# Balloon2.net
KiCad netlist of a schematic drawn in EAGLE
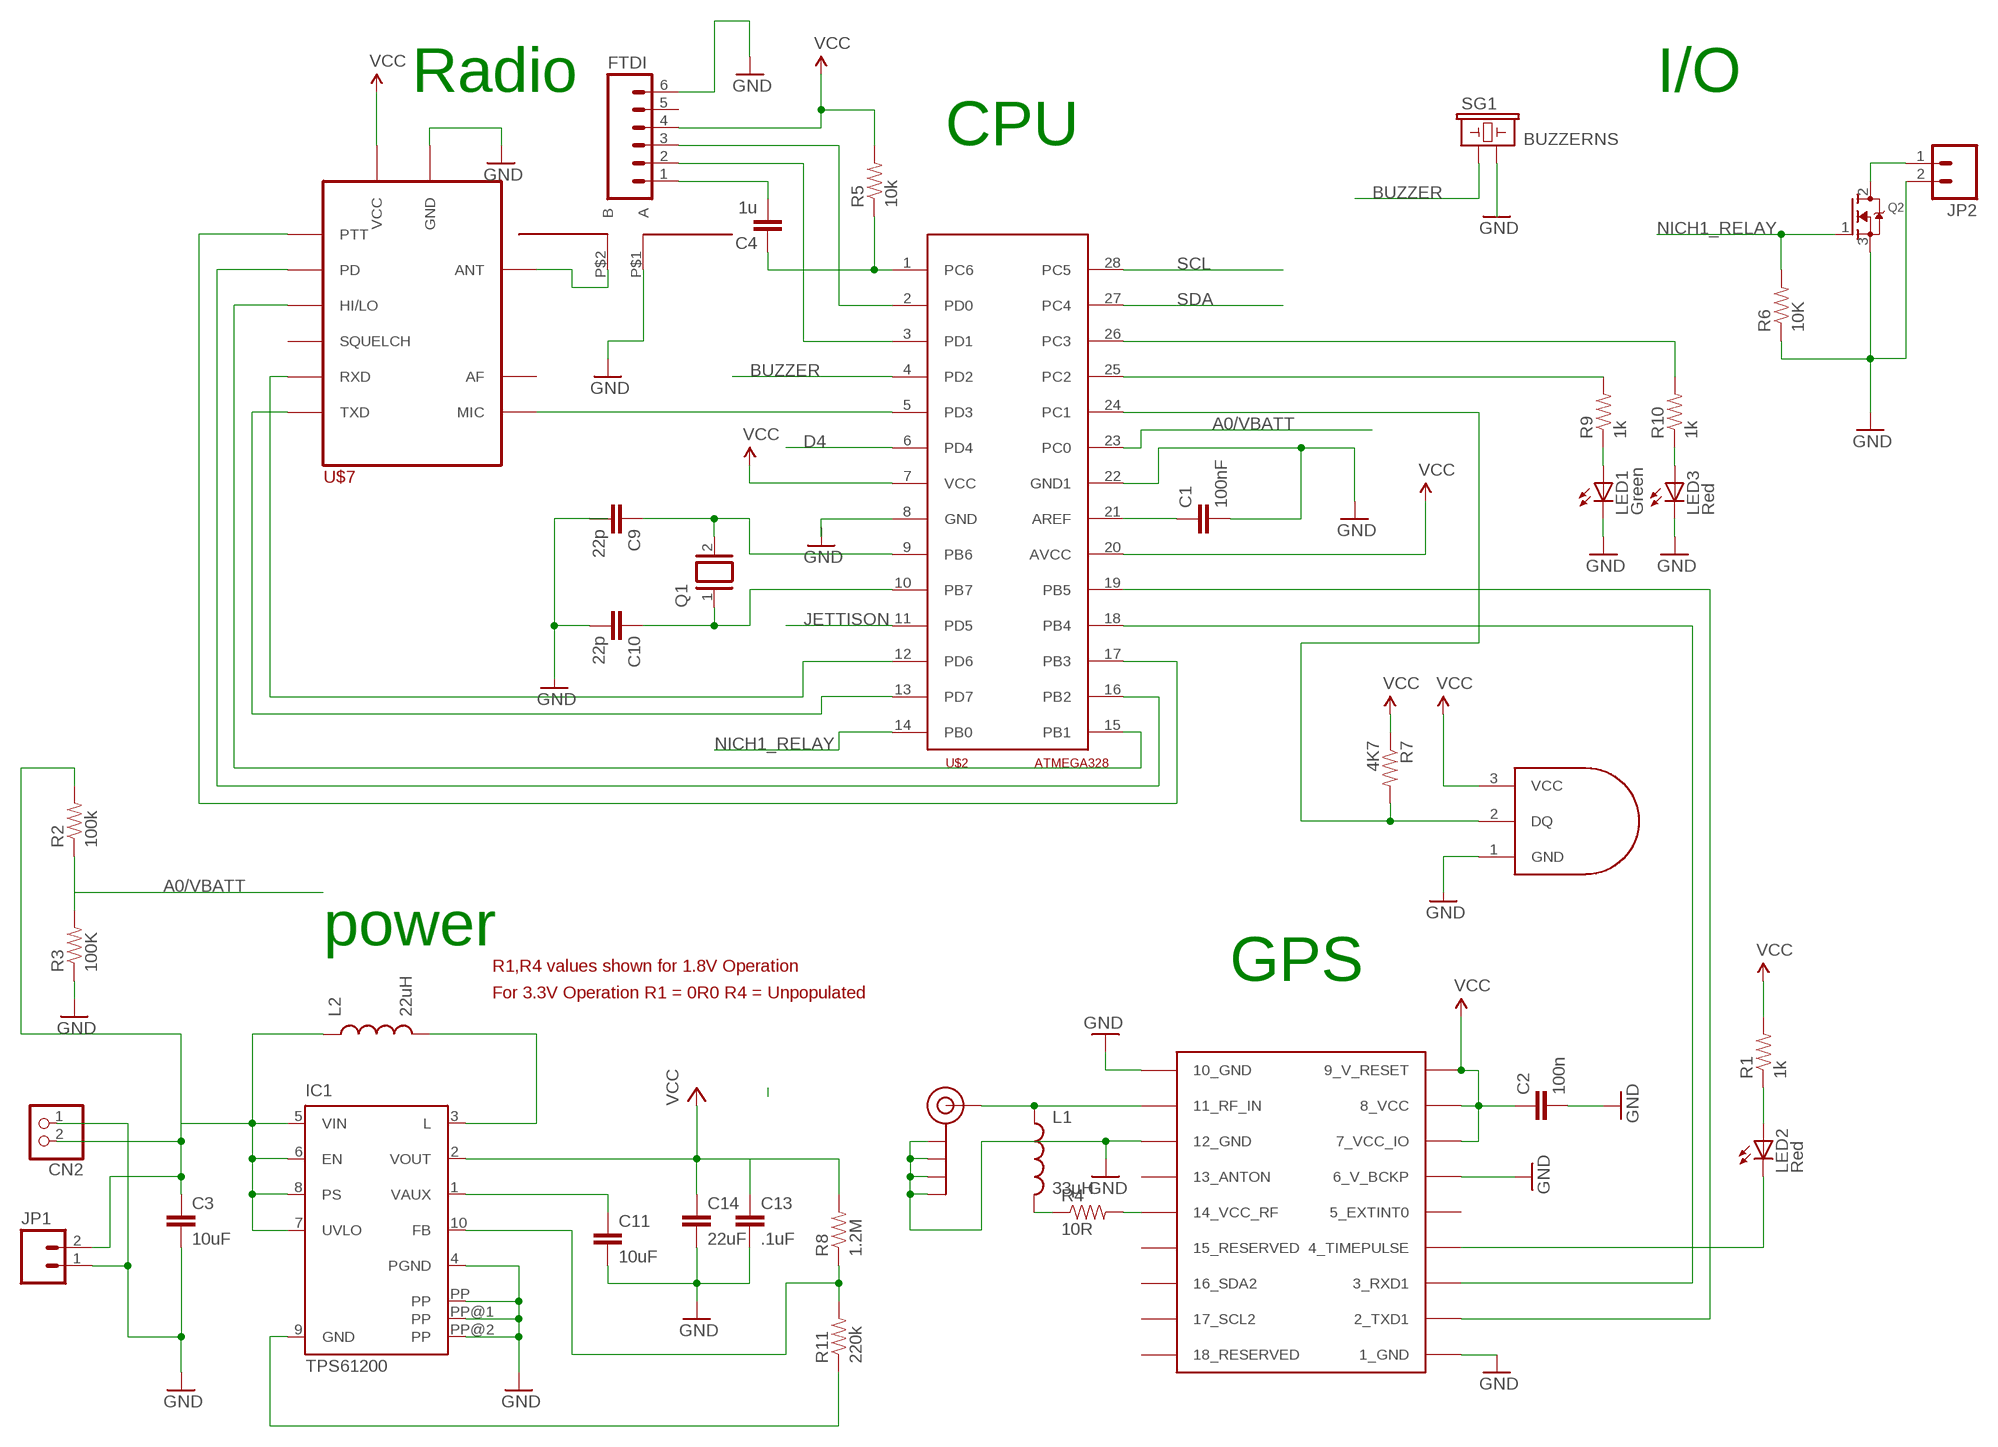
[diagram p0: schematic, sheet 1]

(export (version "E")
  (design (tool "Eeschema 10.0.6"))
  (components
    (comp (ref "C1")
      (value "100nF")
      (footprint "eagle-import:0805")
      (libsource (lib "eagle-import") (part "CAP0805"))
    )
    (comp (ref "C2")
      (value "100n")
      (footprint "eagle-import:0805")
      (libsource (lib "eagle-import") (part "CAP0805"))
    )
    (comp (ref "C3")
      (value "10uF")
      (footprint "eagle-import:0805")
      (libsource (lib "eagle-import") (part "CAP0805"))
    )
    (comp (ref "C4")
      (value "1u")
      (footprint "eagle-import:0805")
      (libsource (lib "eagle-import") (part "CAP0805"))
    )
    (comp (ref "C9")
      (value "22p")
      (footprint "eagle-import:0805")
      (libsource (lib "eagle-import") (part "CAP0805"))
    )
    (comp (ref "C10")
      (value "22p")
      (footprint "eagle-import:0805")
      (libsource (lib "eagle-import") (part "CAP0805"))
    )
    (comp (ref "C11")
      (value "10uF")
      (footprint "eagle-import:0805")
      (libsource (lib "eagle-import") (part "CAP0805"))
    )
    (comp (ref "C13")
      (value ".1uF")
      (footprint "eagle-import:0805")
      (libsource (lib "eagle-import") (part "CAP0805"))
    )
    (comp (ref "C14")
      (value "22uF")
      (footprint "eagle-import:0805")
      (libsource (lib "eagle-import") (part "CAP0805"))
    )
    (comp (ref "CN2")
      (value "JST_2PIN-SMT-RA")
      (footprint "eagle-import:JST-PH-2-SMT-RA")
      (libsource (lib "eagle-import") (part "JST_2PIN-SMT-RA"))
    )
    (comp (ref "FTDI")
      (value "M06SIP")
      (footprint "eagle-import:1X06")
      (libsource (lib "eagle-import") (part "M06SIP"))
    )
    (comp (ref "IC1")
      (value "TPS61200")
      (footprint "eagle-import:S-PDSO-N10")
      (fields (field (name "MPN") "TPS61200DRCT"))
      (libsource (lib "eagle-import") (part "TPS61200"))
    )
    (comp (ref "J$2")
      (value "SMA_EDGE")
      (footprint "eagle-import:SMA-EDGE")
      (libsource (lib "eagle-import") (part "SMA_EDGE"))
    )
    (comp (ref "JP1")
      (value "M02PTH")
      (footprint "eagle-import:1X02")
      (libsource (lib "eagle-import") (part "M02PTH"))
    )
    (comp (ref "JP2")
      (value "M02PTH")
      (footprint "eagle-import:1X02")
      (libsource (lib "eagle-import") (part "M02PTH"))
    )
    (comp (ref "L1")
      (value "33µH")
      (footprint "eagle-import:0805")
      (libsource (lib "eagle-import") (part "INDUCTOR0805"))
    )
    (comp (ref "L2")
      (value "22uH")
      (footprint "eagle-import:INDUCTOR-SRP4020")
      (libsource (lib "eagle-import") (part "INDUCTOR"))
    )
    (comp (ref "LED1")
      (value "Green")
      (footprint "eagle-import:CHIP-LED0805")
      (libsource (lib "eagle-import") (part "LEDCHIP-LED0805"))
    )
    (comp (ref "LED2")
      (value "Red")
      (footprint "eagle-import:CHIP-LED0805")
      (libsource (lib "eagle-import") (part "LEDCHIP-LED0805"))
    )
    (comp (ref "LED3")
      (value "Red")
      (footprint "eagle-import:CHIP-LED0805")
      (libsource (lib "eagle-import") (part "LEDCHIP-LED0805"))
    )
    (comp (ref "Q1")
      (value "XTAL/S")
      (footprint "eagle-import:QS")
      (libsource (lib "eagle-import") (part "XTAL/S"))
    )
    (comp (ref "Q2")
      (value "MOSFET-NGDS_TO220V")
      (footprint "eagle-import:TO220V")
      (libsource (lib "eagle-import") (part "MOSFET-NGDS_TO220V"))
    )
    (comp (ref "R1")
      (value "1k")
      (footprint "eagle-import:0805")
      (libsource (lib "eagle-import") (part "RESISTOR0805-RES"))
    )
    (comp (ref "R2")
      (value "100k")
      (footprint "eagle-import:0805")
      (libsource (lib "eagle-import") (part "RESISTOR0805-RES"))
    )
    (comp (ref "R3")
      (value "100K")
      (footprint "eagle-import:0805")
      (libsource (lib "eagle-import") (part "RESISTOR0805-RES"))
    )
    (comp (ref "R4")
      (value "10R")
      (footprint "eagle-import:0805")
      (libsource (lib "eagle-import") (part "RESISTOR0805-RES"))
    )
    (comp (ref "R5")
      (value "10k")
      (footprint "eagle-import:0805")
      (libsource (lib "eagle-import") (part "RESISTOR0805-RES"))
    )
    (comp (ref "R6")
      (value "10K")
      (footprint "eagle-import:0805")
      (libsource (lib "eagle-import") (part "RESISTOR0805-RES"))
    )
    (comp (ref "R7")
      (value "4K7")
      (footprint "eagle-import:0805")
      (libsource (lib "eagle-import") (part "RESISTOR0805-RES"))
    )
    (comp (ref "R8")
      (value "1.2M")
      (footprint "eagle-import:0805")
      (libsource (lib "eagle-import") (part "RESISTOR0805-RES"))
    )
    (comp (ref "R9")
      (value "1k")
      (footprint "eagle-import:0805")
      (libsource (lib "eagle-import") (part "RESISTOR0805-RES"))
    )
    (comp (ref "R10")
      (value "1k")
      (footprint "eagle-import:0805")
      (libsource (lib "eagle-import") (part "RESISTOR0805-RES"))
    )
    (comp (ref "R11")
      (value "220k")
      (footprint "eagle-import:0805")
      (libsource (lib "eagle-import") (part "RESISTOR0805-RES"))
    )
    (comp (ref "SG1")
      (value "BUZZERNS")
      (footprint "eagle-import:BUZZER-12MM-NS")
      (libsource (lib "eagle-import") (part "BUZZERNS"))
    )
    (comp (ref "U$1")
      (value "UBLOX_MAX")
      (footprint "eagle-import:UBLOX_MAX")
      (libsource (lib "eagle-import") (part "UBLOX_MAX"))
    )
    (comp (ref "U$2")
      (value "ATMEGA328")
      (footprint "eagle-import:DIL28")
      (libsource (lib "eagle-import") (part "ATMEGA328"))
    )
    (comp (ref "U$3")
      (value "DS18B20")
      (footprint "eagle-import:TO-92")
      (libsource (lib "eagle-import") (part "DS18B20"))
    )
    (comp (ref "U$4")
      (value "SOLDER-DIPOLE")
      (footprint "eagle-import:SOLDERED-DIPOLE-5MM")
      (libsource (lib "eagle-import") (part "SOLDER-DIPOLE"))
    )
    (comp (ref "U$7")
      (value "DORJI")
      (footprint "eagle-import:DORJI")
      (libsource (lib "eagle-import") (part "DORJI"))
    )
  )
  (nets
    (net (code "1") (name "/A0{slash}VBATT") (class "Default")
      (node (ref "R2") (pin "1") (pinfunction "1_1") (pintype "passive"))
      (node (ref "R3") (pin "2") (pinfunction "2_2") (pintype "passive"))
      (node (ref "U$2") (pin "23") (pinfunction "PC0_23") (pintype "bidirectional"))
    )
    (net (code "2") (name "/BUZZER") (class "Default")
      (node (ref "SG1") (pin "+") (pinfunction "1_+") (pintype "passive"))
      (node (ref "U$2") (pin "4") (pinfunction "PD2_4") (pintype "bidirectional"))
    )
    (net (code "3") (name "/D4") (class "Default")
      (node (ref "U$2") (pin "6") (pinfunction "PD4_6") (pintype "bidirectional"))
    )
    (net (code "4") (name "/JETTISON") (class "Default")
      (node (ref "U$2") (pin "11") (pinfunction "PD5_11") (pintype "bidirectional"))
    )
    (net (code "5") (name "/NICH1_RELAY") (class "Default")
      (node (ref "Q2") (pin "1") (pinfunction "G_1") (pintype "bidirectional"))
      (node (ref "R6") (pin "2") (pinfunction "2_2") (pintype "passive"))
      (node (ref "U$2") (pin "14") (pinfunction "PB0_14") (pintype "bidirectional"))
    )
    (net (code "6") (name "/SCL") (class "Default")
      (node (ref "U$2") (pin "28") (pinfunction "PC5_28") (pintype "bidirectional"))
    )
    (net (code "7") (name "/SDA") (class "Default")
      (node (ref "U$2") (pin "27") (pinfunction "PC4_27") (pintype "bidirectional"))
    )
    (net (code "8") (name "GND") (class "Default")
      (node (ref "C1") (pin "2") (pinfunction "2_2") (pintype "passive"))
      (node (ref "C11") (pin "2") (pinfunction "2_2") (pintype "passive"))
      (node (ref "C13") (pin "2") (pinfunction "2_2") (pintype "passive"))
      (node (ref "C14") (pin "2") (pinfunction "2_2") (pintype "passive"))
      (node (ref "C2") (pin "2") (pinfunction "2_2") (pintype "passive"))
      (node (ref "C3") (pin "2") (pinfunction "2_2") (pintype "passive"))
      (node (ref "CN2") (pin "1") (pinfunction "2_1") (pintype "passive"))
      (node (ref "FTDI") (pin "6") (pinfunction "6_6") (pintype "passive"))
      (node (ref "IC1") (pin "4") (pinfunction "PGND_4") (pintype "power_in"))
      (node (ref "IC1") (pin "PP") (pinfunction "PP_PP") (pintype "power_in"))
      (node (ref "IC1") (pin "PP@1") (pinfunction "PP_PP@1") (pintype "power_in"))
      (node (ref "IC1") (pin "PP@2") (pinfunction "PP_PP@2") (pintype "power_in"))
      (node (ref "J$2") (pin "GND@0") (pinfunction "GND_GND@0") (pintype "bidirectional"))
      (node (ref "J$2") (pin "GND@1") (pinfunction "GND_GND@1") (pintype "bidirectional"))
      (node (ref "J$2") (pin "GND@2") (pinfunction "GND_GND@2") (pintype "bidirectional"))
      (node (ref "J$2") (pin "GND@3") (pinfunction "GND_GND@3") (pintype "bidirectional"))
      (node (ref "JP1") (pin "1") (pinfunction "1_1") (pintype "passive"))
      (node (ref "JP2") (pin "2") (pinfunction "2_2") (pintype "passive"))
      (node (ref "LED1") (pin "C") (pinfunction "C_C") (pintype "passive"))
      (node (ref "LED3") (pin "C") (pinfunction "C_C") (pintype "passive"))
      (node (ref "Q2") (pin "3") (pinfunction "S_3") (pintype "bidirectional"))
      (node (ref "R3") (pin "1") (pinfunction "1_1") (pintype "passive"))
      (node (ref "R6") (pin "1") (pinfunction "1_1") (pintype "passive"))
      (node (ref "U$1") (pin "10_GND") (pinfunction "10_GND_10_GND") (pintype "power_in"))
      (node (ref "U$1") (pin "12_GND") (pinfunction "12_GND_12_GND") (pintype "power_in"))
      (node (ref "U$1") (pin "1_GND") (pinfunction "1_GND_1_GND") (pintype "power_in"))
      (node (ref "U$1") (pin "6_V_BCKP") (pinfunction "6_V_BCKP_6_V_BCKP") (pintype "bidirectional"))
      (node (ref "U$2") (pin "22") (pinfunction "GND1_22") (pintype "bidirectional"))
      (node (ref "U$4") (pin "P$1") (pinfunction "A_P$1") (pintype "bidirectional"))
      (node (ref "U$7") (pin "P$10") (pinfunction "GND_P$10") (pintype "bidirectional"))
      (node (ref "U$7") (pin "P$9") (pinfunction "GND_P$9") (pintype "bidirectional"))
    )
    (net (code "9") (name "Net-(C4-Pad2)") (class "Default")
      (node (ref "C4") (pin "2") (pinfunction "2_2") (pintype "passive"))
      (node (ref "FTDI") (pin "1") (pinfunction "1_1") (pintype "passive"))
    )
    (net (code "10") (name "Net-(CN2-1)") (class "Default")
      (node (ref "C3") (pin "1") (pinfunction "1_1") (pintype "passive"))
      (node (ref "CN2") (pin "2") (pinfunction "1_2") (pintype "passive"))
      (node (ref "IC1") (pin "5") (pinfunction "VIN_5") (pintype "input"))
      (node (ref "IC1") (pin "6") (pinfunction "EN_6") (pintype "input"))
      (node (ref "IC1") (pin "7") (pinfunction "UVLO_7") (pintype "input"))
      (node (ref "IC1") (pin "8") (pinfunction "PS_8") (pintype "input"))
      (node (ref "JP1") (pin "2") (pinfunction "2_2") (pintype "passive"))
      (node (ref "L2") (pin "P$1") (pinfunction "1_P$1") (pintype "passive"))
      (node (ref "R2") (pin "2") (pinfunction "2_2") (pintype "passive"))
    )
    (net (code "11") (name "Net-(IC1-FB)") (class "Default")
      (node (ref "IC1") (pin "10") (pinfunction "FB_10") (pintype "input"))
      (node (ref "R11") (pin "2") (pinfunction "2_2") (pintype "passive"))
      (node (ref "R8") (pin "1") (pinfunction "1_1") (pintype "passive"))
    )
    (net (code "12") (name "Net-(IC1-GND)") (class "Default")
      (node (ref "IC1") (pin "9") (pinfunction "GND_9") (pintype "power_in"))
      (node (ref "R11") (pin "1") (pinfunction "1_1") (pintype "passive"))
    )
    (net (code "13") (name "Net-(IC1-L)") (class "Default")
      (node (ref "IC1") (pin "3") (pinfunction "L_3") (pintype "input"))
      (node (ref "L2") (pin "P$2") (pinfunction "2_P$2") (pintype "passive"))
    )
    (net (code "14") (name "Net-(IC1-VAUX)") (class "Default")
      (node (ref "C11") (pin "1") (pinfunction "1_1") (pintype "passive"))
      (node (ref "IC1") (pin "1") (pinfunction "VAUX_1") (pintype "bidirectional"))
    )
    (net (code "15") (name "Net-(J$2-SIGNAL)") (class "Default")
      (node (ref "J$2") (pin "SIG") (pinfunction "SIGNAL_SIG") (pintype "bidirectional"))
      (node (ref "L1") (pin "1") (pinfunction "1_1") (pintype "passive"))
      (node (ref "U$1") (pin "11_RF_IN") (pinfunction "11_RF_IN_11_RF_IN") (pintype "bidirectional"))
    )
    (net (code "16") (name "Net-(L1-Pad2)") (class "Default")
      (node (ref "L1") (pin "2") (pinfunction "2_2") (pintype "passive"))
      (node (ref "R4") (pin "1") (pinfunction "1_1") (pintype "passive"))
    )
    (net (code "17") (name "Net-(LED1-PadA)") (class "Default")
      (node (ref "LED1") (pin "A") (pinfunction "A_A") (pintype "passive"))
      (node (ref "R9") (pin "1") (pinfunction "1_1") (pintype "passive"))
    )
    (net (code "18") (name "Net-(LED2-PadA)") (class "Default")
      (node (ref "LED2") (pin "A") (pinfunction "A_A") (pintype "passive"))
      (node (ref "R1") (pin "1") (pinfunction "1_1") (pintype "passive"))
    )
    (net (code "19") (name "Net-(LED2-PadC)") (class "Default")
      (node (ref "LED2") (pin "C") (pinfunction "C_C") (pintype "passive"))
      (node (ref "U$1") (pin "4_TIMEPULSE") (pinfunction "4_TIMEPULSE_4_TIMEPULSE") (pintype "bidirectional"))
    )
    (net (code "20") (name "Net-(LED3-PadA)") (class "Default")
      (node (ref "LED3") (pin "A") (pinfunction "A_A") (pintype "passive"))
      (node (ref "R10") (pin "1") (pinfunction "1_1") (pintype "passive"))
    )
    (net (code "21") (name "Net-(Q2-D)") (class "Default")
      (node (ref "JP2") (pin "1") (pinfunction "1_1") (pintype "passive"))
      (node (ref "Q2") (pin "2") (pinfunction "D_2") (pintype "bidirectional"))
    )
    (net (code "22") (name "Net-(R4-Pad2)") (class "Default")
      (node (ref "R4") (pin "2") (pinfunction "2_2") (pintype "passive"))
      (node (ref "U$1") (pin "14_VCC_RF") (pinfunction "14_VCC_RF_14_VCC_RF") (pintype "bidirectional"))
    )
    (net (code "23") (name "Net-(U$2-AREF)") (class "Default")
      (node (ref "C1") (pin "1") (pinfunction "1_1") (pintype "passive"))
      (node (ref "U$2") (pin "21") (pinfunction "AREF_21") (pintype "bidirectional"))
    )
    (net (code "24") (name "Net-(U$2-PB1)") (class "Default")
      (node (ref "U$2") (pin "15") (pinfunction "PB1_15") (pintype "bidirectional"))
      (node (ref "U$7") (pin "P$7") (pinfunction "HI/LO_P$7") (pintype "bidirectional"))
    )
    (net (code "25") (name "Net-(U$2-PB2)") (class "Default")
      (node (ref "U$2") (pin "16") (pinfunction "PB2_16") (pintype "bidirectional"))
      (node (ref "U$7") (pin "P$6") (pinfunction "PD_P$6") (pintype "bidirectional"))
    )
    (net (code "26") (name "Net-(U$2-PB3)") (class "Default")
      (node (ref "U$2") (pin "17") (pinfunction "PB3_17") (pintype "bidirectional"))
      (node (ref "U$7") (pin "P$5") (pinfunction "PTT_P$5") (pintype "bidirectional"))
    )
    (net (code "27") (name "Net-(U$2-PB4)") (class "Default")
      (node (ref "U$1") (pin "3_RXD1") (pinfunction "3_RXD1_3_RXD1") (pintype "bidirectional"))
      (node (ref "U$2") (pin "18") (pinfunction "PB4_18") (pintype "bidirectional"))
    )
    (net (code "28") (name "Net-(U$2-PB5)") (class "Default")
      (node (ref "U$1") (pin "2_TXD1") (pinfunction "2_TXD1_2_TXD1") (pintype "bidirectional"))
      (node (ref "U$2") (pin "19") (pinfunction "PB5_19") (pintype "bidirectional"))
    )
    (net (code "29") (name "Net-(U$2-PB6)") (class "Default")
      (node (ref "C9") (pin "1") (pinfunction "1_1") (pintype "passive"))
      (node (ref "Q1") (pin "2") (pinfunction "2_2") (pintype "passive"))
      (node (ref "U$2") (pin "9") (pinfunction "PB6_9") (pintype "bidirectional"))
    )
    (net (code "30") (name "Net-(U$2-PB7)") (class "Default")
      (node (ref "C10") (pin "1") (pinfunction "1_1") (pintype "passive"))
      (node (ref "Q1") (pin "1") (pinfunction "1_1") (pintype "passive"))
      (node (ref "U$2") (pin "10") (pinfunction "PB7_10") (pintype "bidirectional"))
    )
    (net (code "31") (name "Net-(U$2-PC1)") (class "Default")
      (node (ref "R7") (pin "2") (pinfunction "2_2") (pintype "passive"))
      (node (ref "U$2") (pin "24") (pinfunction "PC1_24") (pintype "bidirectional"))
      (node (ref "U$3") (pin "2") (pinfunction "DQ_2") (pintype "bidirectional"))
    )
    (net (code "32") (name "Net-(U$2-PC2)") (class "Default")
      (node (ref "R9") (pin "2") (pinfunction "2_2") (pintype "passive"))
      (node (ref "U$2") (pin "25") (pinfunction "PC2_25") (pintype "bidirectional"))
    )
    (net (code "33") (name "Net-(U$2-PC3)") (class "Default")
      (node (ref "R10") (pin "2") (pinfunction "2_2") (pintype "passive"))
      (node (ref "U$2") (pin "26") (pinfunction "PC3_26") (pintype "bidirectional"))
    )
    (net (code "34") (name "Net-(U$2-PC6)") (class "Default")
      (node (ref "C4") (pin "1") (pinfunction "1_1") (pintype "passive"))
      (node (ref "R5") (pin "1") (pinfunction "1_1") (pintype "passive"))
      (node (ref "U$2") (pin "1") (pinfunction "PC6_1") (pintype "bidirectional"))
    )
    (net (code "35") (name "Net-(U$2-PD0)") (class "Default")
      (node (ref "FTDI") (pin "3") (pinfunction "3_3") (pintype "passive"))
      (node (ref "U$2") (pin "2") (pinfunction "PD0_2") (pintype "bidirectional"))
    )
    (net (code "36") (name "Net-(U$2-PD1)") (class "Default")
      (node (ref "FTDI") (pin "2") (pinfunction "2_2") (pintype "passive"))
      (node (ref "U$2") (pin "3") (pinfunction "PD1_3") (pintype "bidirectional"))
    )
    (net (code "37") (name "Net-(U$2-PD3)") (class "Default")
      (node (ref "U$2") (pin "5") (pinfunction "PD3_5") (pintype "bidirectional"))
      (node (ref "U$7") (pin "P$18") (pinfunction "MIC_P$18") (pintype "bidirectional"))
    )
    (net (code "38") (name "Net-(U$2-PD6)") (class "Default")
      (node (ref "U$2") (pin "12") (pinfunction "PD6_12") (pintype "bidirectional"))
      (node (ref "U$7") (pin "P$16") (pinfunction "RXD_P$16") (pintype "bidirectional"))
    )
    (net (code "39") (name "Net-(U$2-PD7)") (class "Default")
      (node (ref "U$2") (pin "13") (pinfunction "PD7_13") (pintype "bidirectional"))
      (node (ref "U$7") (pin "P$17") (pinfunction "TXD_P$17") (pintype "bidirectional"))
    )
    (net (code "40") (name "Net-(U$4-B)") (class "Default")
      (node (ref "U$4") (pin "P$2") (pinfunction "B_P$2") (pintype "bidirectional"))
      (node (ref "U$7") (pin "P$12") (pinfunction "ANT_P$12") (pintype "bidirectional"))
    )
    (net (code "41") (name "VCC") (class "Default")
      (node (ref "C13") (pin "1") (pinfunction "1_1") (pintype "passive"))
      (node (ref "C14") (pin "1") (pinfunction "1_1") (pintype "passive"))
      (node (ref "C2") (pin "1") (pinfunction "1_1") (pintype "passive"))
      (node (ref "FTDI") (pin "4") (pinfunction "4_4") (pintype "passive"))
      (node (ref "IC1") (pin "2") (pinfunction "VOUT_2") (pintype "passive"))
      (node (ref "R1") (pin "2") (pinfunction "2_2") (pintype "passive"))
      (node (ref "R5") (pin "2") (pinfunction "2_2") (pintype "passive"))
      (node (ref "R7") (pin "1") (pinfunction "1_1") (pintype "passive"))
      (node (ref "R8") (pin "2") (pinfunction "2_2") (pintype "passive"))
      (node (ref "U$1") (pin "7_VCC_IO") (pinfunction "7_VCC_IO_7_VCC_IO") (pintype "power_in"))
      (node (ref "U$1") (pin "8_VCC") (pinfunction "8_VCC_8_VCC") (pintype "power_in"))
      (node (ref "U$1") (pin "9_V_RESET") (pinfunction "9_V_RESET_9_V_RESET") (pintype "power_in"))
      (node (ref "U$2") (pin "20") (pinfunction "AVCC_20") (pintype "bidirectional"))
      (node (ref "U$2") (pin "7") (pinfunction "VCC_7") (pintype "bidirectional"))
      (node (ref "U$3") (pin "3") (pinfunction "VCC_3") (pintype "bidirectional"))
      (node (ref "U$7") (pin "P$8") (pinfunction "VCC_P$8") (pintype "bidirectional"))
    )
    (net (code "42") (name "unconnected-(C9-Pad2)") (class "Default")
      (node (ref "C9") (pin "2") (pinfunction "2_2") (pintype "passive"))
    )
    (net (code "43") (name "unconnected-(C10-Pad2)") (class "Default")
      (node (ref "C10") (pin "2") (pinfunction "2_2") (pintype "passive"))
    )
    (net (code "44") (name "unconnected-(FTDI-Pad5)") (class "Default")
      (node (ref "FTDI") (pin "5") (pinfunction "5_5") (pintype "passive"))
    )
    (net (code "45") (name "unconnected-(SG1-2-Pad-)") (class "Default")
      (node (ref "SG1") (pin "-") (pinfunction "2_-") (pintype "passive"))
    )
    (net (code "46") (name "unconnected-(U$1-Pad5_EXTINT0)") (class "Default")
      (node (ref "U$1") (pin "5_EXTINT0") (pinfunction "5_EXTINT0_5_EXTINT0") (pintype "bidirectional"))
    )
    (net (code "47") (name "unconnected-(U$1-Pad13_ANTON)") (class "Default")
      (node (ref "U$1") (pin "13_ANTON") (pinfunction "13_ANTON_13_ANTON") (pintype "bidirectional"))
    )
    (net (code "48") (name "unconnected-(U$1-Pad15_RESERVED)") (class "Default")
      (node (ref "U$1") (pin "15_RESERVED") (pinfunction "15_RESERVED_15_RESERVED") (pintype "bidirectional"))
    )
    (net (code "49") (name "unconnected-(U$1-Pad16_SDA2)") (class "Default")
      (node (ref "U$1") (pin "16_SDA2") (pinfunction "16_SDA2_16_SDA2") (pintype "bidirectional"))
    )
    (net (code "50") (name "unconnected-(U$1-Pad17_SCL2)") (class "Default")
      (node (ref "U$1") (pin "17_SCL2") (pinfunction "17_SCL2_17_SCL2") (pintype "bidirectional"))
    )
    (net (code "51") (name "unconnected-(U$1-Pad18_RESERVED)") (class "Default")
      (node (ref "U$1") (pin "18_RESERVED") (pinfunction "18_RESERVED_18_RESERVED") (pintype "bidirectional"))
    )
    (net (code "52") (name "unconnected-(U$2-GND-Pad8)") (class "Default")
      (node (ref "U$2") (pin "8") (pinfunction "GND_8") (pintype "bidirectional"))
    )
    (net (code "53") (name "unconnected-(U$3-GND-Pad1)") (class "Default")
      (node (ref "U$3") (pin "1") (pinfunction "GND_1") (pintype "bidirectional"))
    )
    (net (code "54") (name "unconnected-(U$7-AF-PadP$3)") (class "Default")
      (node (ref "U$7") (pin "P$3") (pinfunction "AF_P$3") (pintype "bidirectional"))
    )
    (net (code "55") (name "unconnected-(U$7-SQUELCH-PadP$1)") (class "Default")
      (node (ref "U$7") (pin "P$1") (pinfunction "SQUELCH_P$1") (pintype "bidirectional"))
    )
  )
)
